# SCH_card_2025-04-24.net
KiCad netlist of a schematic drawn in EasyEDA
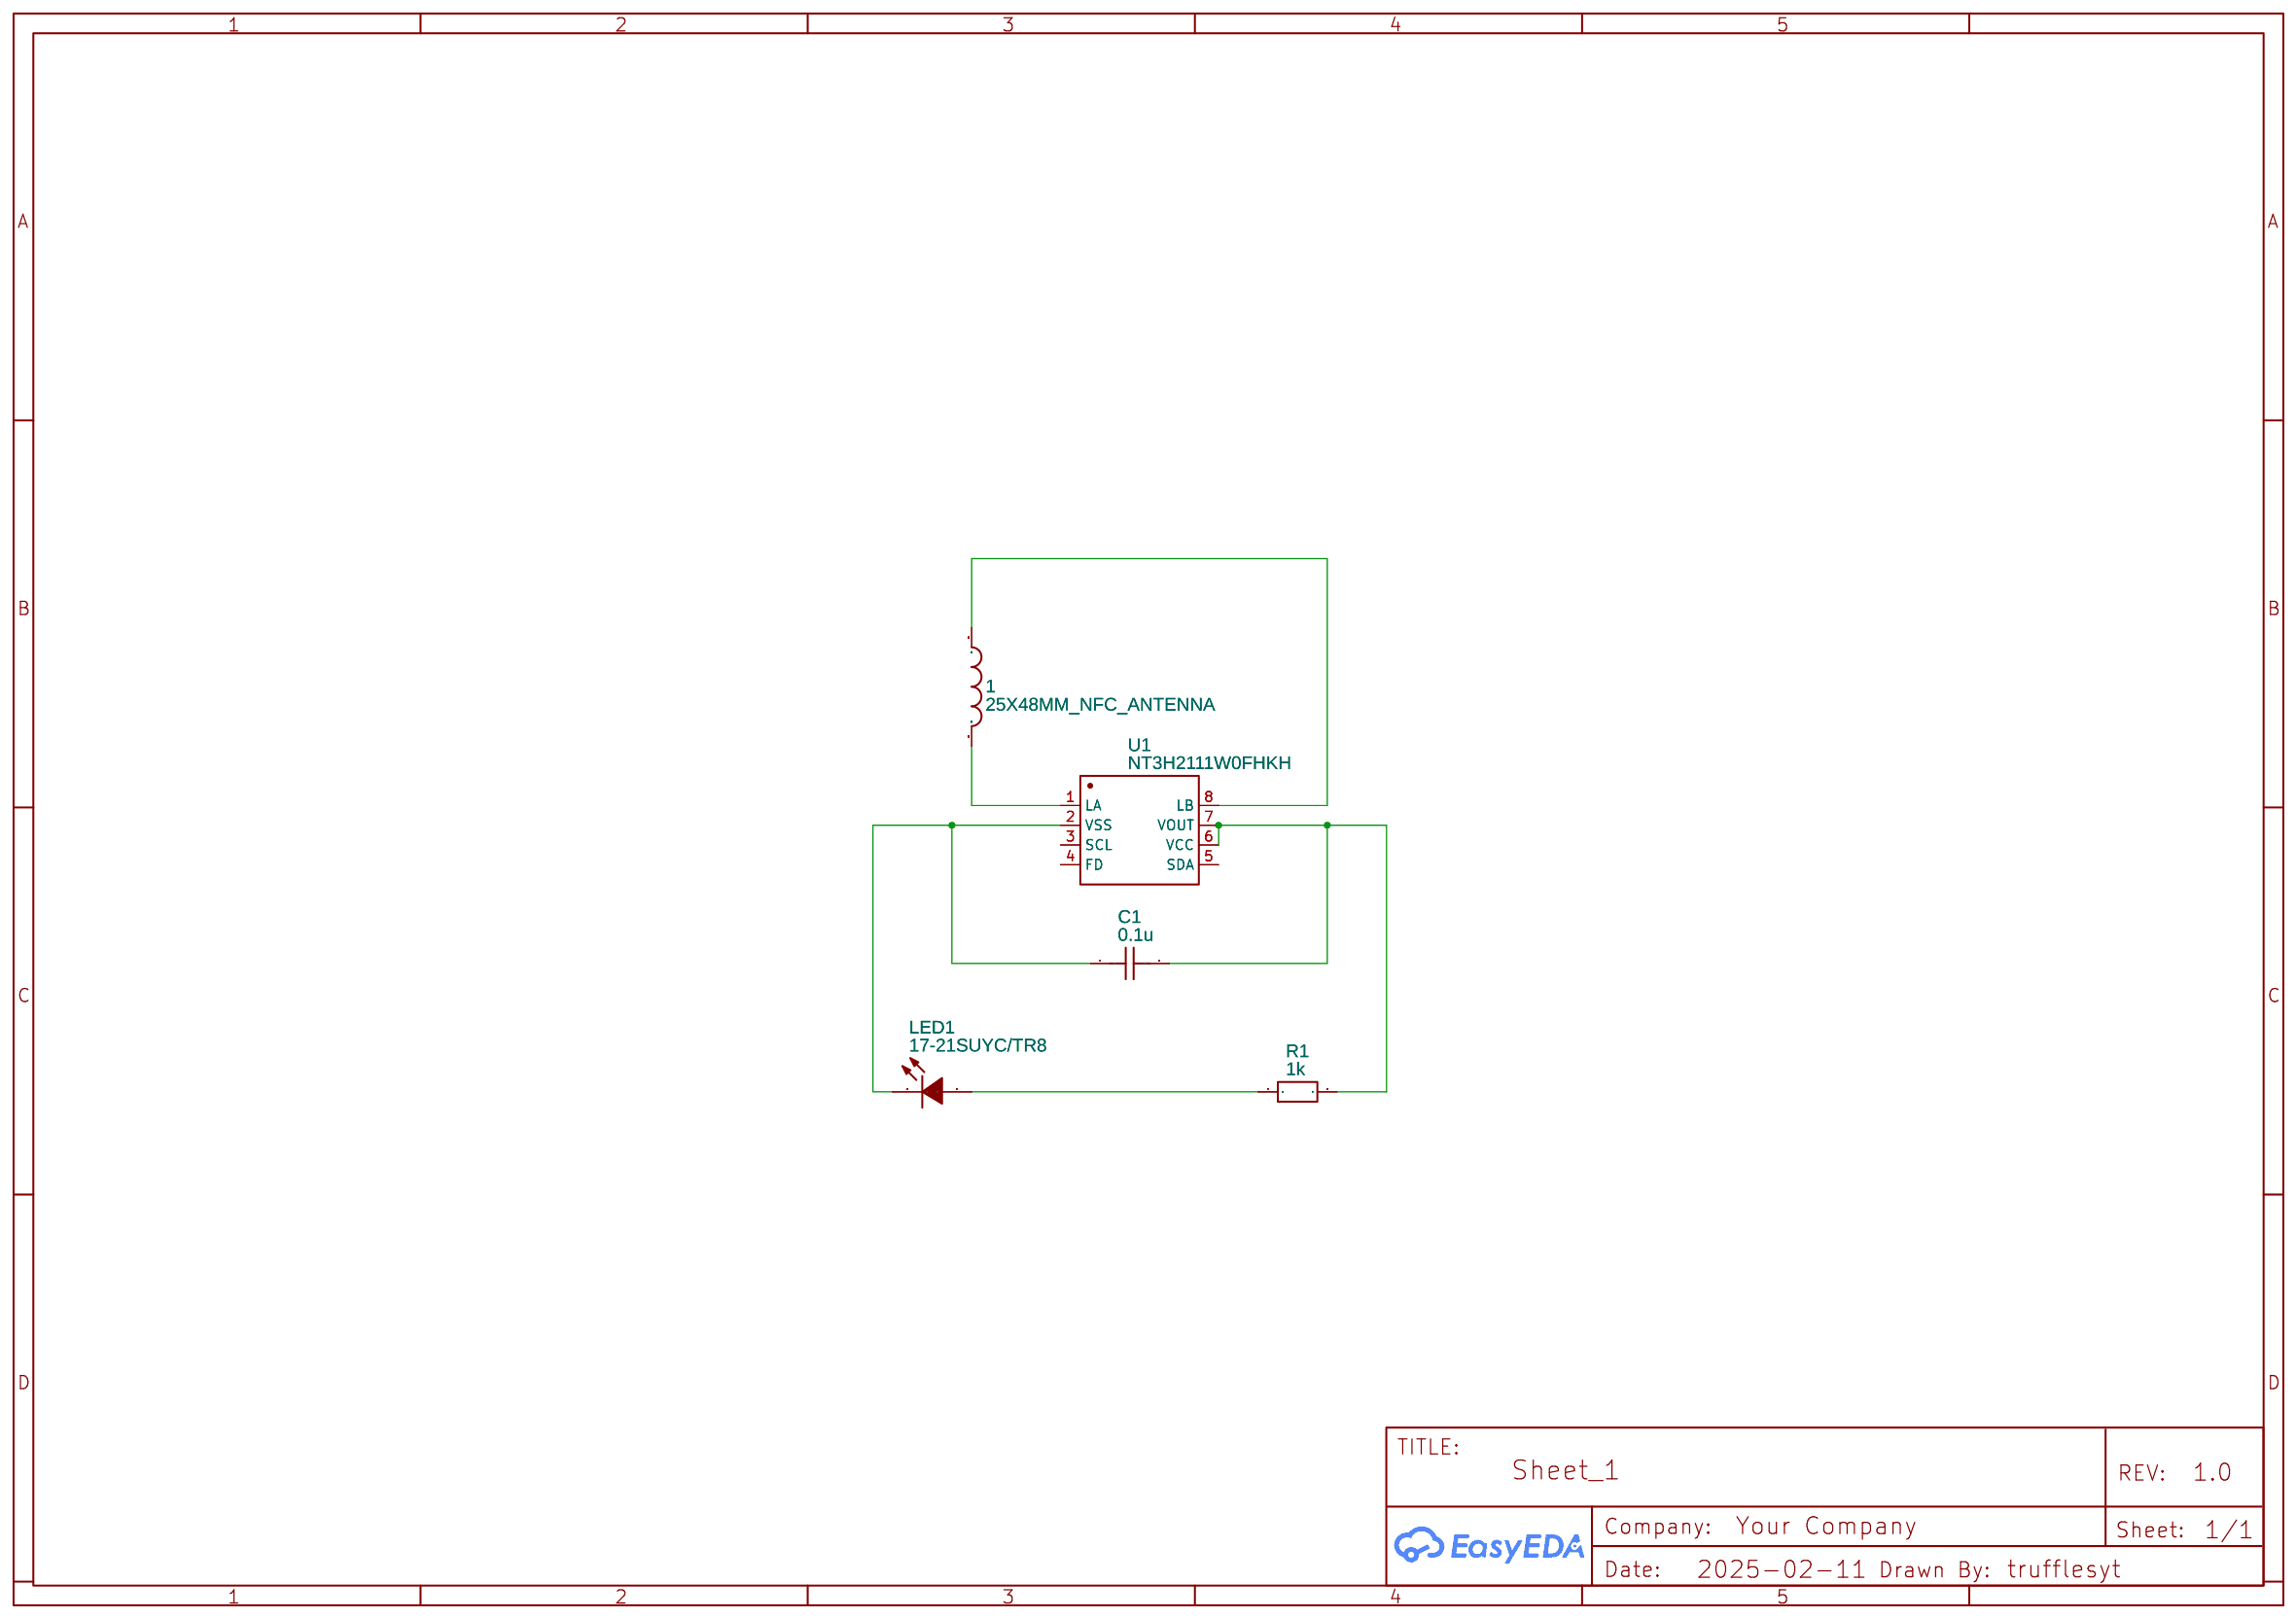
[diagram p0: schematic sheet]

(export (version "E")
  (design (tool "Eeschema 10.0.6"))
  (components
    (comp (ref "1") (value "25X48MM_NFC_ANTENNA") (libsource (lib "") (part "25X48MM_NFC_ANTENNA")))
    (comp (ref "C1") (value "0.1u") (libsource (lib "") (part "C_0603_US")))
    (comp (ref "LED1")
      (value "17-21SUYC/TR8")
      (fields (field (name "Manufacturer Part") "KT-0805黄灯") (field (name "Manufacturer") "KENTO"))
      (libsource (lib "") (part "17-21SUYC/TR8"))
    )
    (comp (ref "R1") (value "1k") (libsource (lib "") (part "R_0603_EU")))
    (comp (ref "U1")
      (value "NT3H2111W0FHKH")
      (fields (field (name "Manufacturer") "NXP(恩智浦)"))
      (libsource (lib "") (part "NT3H2111W0FHKH"))
    )
  )
  (nets
    (net (code "1") (name "Net-(LED1-+)") (class "Default")
      (node (ref "LED1") (pin "1") (pinfunction "+_1") (pintype "unspecified"))
      (node (ref "R1") (pin "1") (pinfunction "1_1") (pintype "unspecified"))
    )
    (net (code "2") (name "Net-(LED1--)") (class "Default")
      (node (ref "C1") (pin "1") (pinfunction "1_1") (pintype "unspecified"))
      (node (ref "LED1") (pin "2") (pinfunction "-_2") (pintype "unspecified"))
      (node (ref "U1") (pin "2") (pinfunction "VSS_2") (pintype "unspecified"))
    )
    (net (code "3") (name "Net-(U1-LA)") (class "Default")
      (node (ref "1") (pin "P$2") (pinfunction "P$2_P$2") (pintype "bidirectional"))
      (node (ref "U1") (pin "1") (pinfunction "LA_1") (pintype "unspecified"))
    )
    (net (code "4") (name "Net-(U1-LB)") (class "Default")
      (node (ref "1") (pin "P$1") (pinfunction "P$1_P$1") (pintype "bidirectional"))
      (node (ref "U1") (pin "8") (pinfunction "LB_8") (pintype "unspecified"))
    )
    (net (code "5") (name "Net-(U1-VCC)") (class "Default")
      (node (ref "C1") (pin "2") (pinfunction "2_2") (pintype "unspecified"))
      (node (ref "R1") (pin "2") (pinfunction "2_2") (pintype "unspecified"))
      (node (ref "U1") (pin "6") (pinfunction "VCC_6") (pintype "unspecified"))
      (node (ref "U1") (pin "7") (pinfunction "VOUT_7") (pintype "unspecified"))
    )
    (net (code "6") (name "unconnected-(U1-FD-Pad4)") (class "Default")
      (node (ref "U1") (pin "4") (pinfunction "FD_4") (pintype "unspecified"))
    )
    (net (code "7") (name "unconnected-(U1-SCL-Pad3)") (class "Default")
      (node (ref "U1") (pin "3") (pinfunction "SCL_3") (pintype "unspecified"))
    )
    (net (code "8") (name "unconnected-(U1-SDA-Pad5)") (class "Default")
      (node (ref "U1") (pin "5") (pinfunction "SDA_5") (pintype "unspecified"))
    )
  )
)
